# Grove_-_Barometer_Sensor_BME280_v1_0.net
KiCad netlist of a schematic drawn in EAGLE
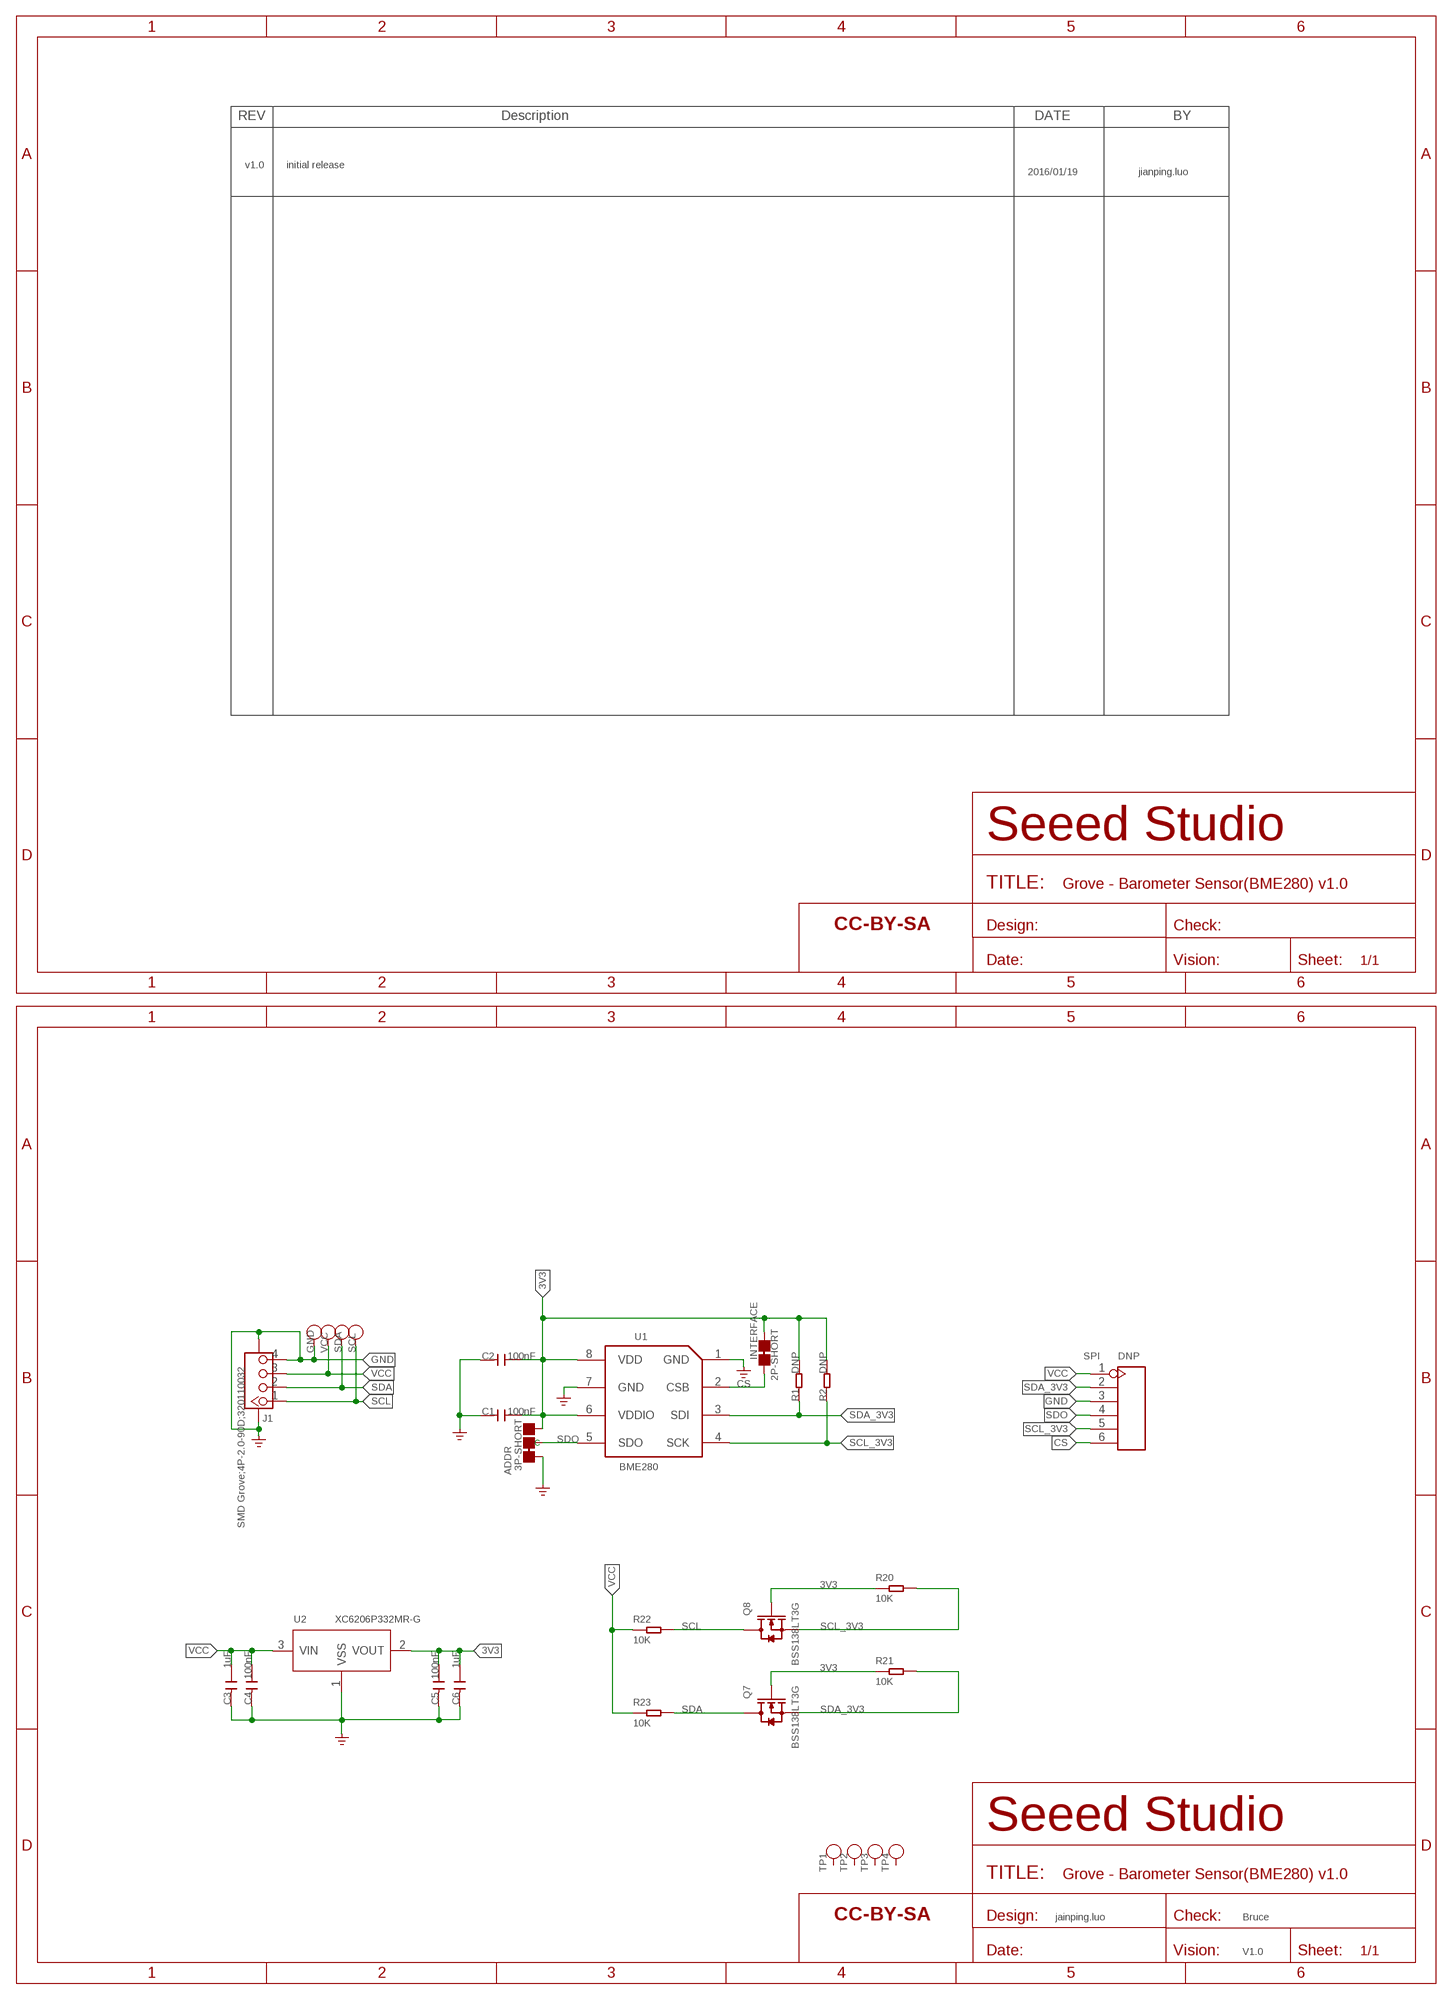
[diagram p0: schematic, sheet 1]

(export (version "E")
  (design (tool "Eeschema 10.0.6"))
  (components
    (comp (ref "ADDR")
      (value "3P-SHORT")
      (footprint "eagle-import:3P-SMD-SHORT")
      (libsource (lib "eagle-import") (part "JUMPER-3P-SHORT"))
    )
    (comp (ref "C1")
      (value "100nF")
      (footprint "eagle-import:C0603")
      (libsource (lib "eagle-import") (part "CAP-0603"))
    )
    (comp (ref "C2")
      (value "100nF")
      (footprint "eagle-import:C0603")
      (libsource (lib "eagle-import") (part "CAP-0603"))
    )
    (comp (ref "C3")
      (value "1uF")
      (footprint "eagle-import:C0603")
      (libsource (lib "eagle-import") (part "CAP-0603"))
    )
    (comp (ref "C4")
      (value "100nF")
      (footprint "eagle-import:C0603")
      (libsource (lib "eagle-import") (part "CAP-0603"))
    )
    (comp (ref "C5")
      (value "100nF")
      (footprint "eagle-import:C0603")
      (libsource (lib "eagle-import") (part "CAP-0603"))
    )
    (comp (ref "C6")
      (value "1uF")
      (footprint "eagle-import:C0603")
      (libsource (lib "eagle-import") (part "CAP-0603"))
    )
    (comp (ref "FR1")
      (value "SEEEDSTUDIO-OPEN-SCH-FRAME")
      (footprint "eagle-import:SEEEDSTUDIO-PCB-FRAME")
      (libsource (lib "eagle-import") (part "SEEEDSTUDIO-OPEN-SCH-FRAME"))
    )
    (comp (ref "FR2")
      (value "SEEEDSTUDIO-OPEN-SCH-FRAME")
      (footprint "eagle-import:SEEEDSTUDIO-PCB-FRAME")
      (libsource (lib "eagle-import") (part "SEEEDSTUDIO-OPEN-SCH-FRAME"))
    )
    (comp (ref "GND")
      (value "TEST-POINT'4545'")
      (footprint "eagle-import:TP-D45MIL")
      (fields (field (name "PARTNO") "DNP"))
      (libsource (lib "eagle-import") (part "TEST-POINT'4545'"))
    )
    (comp (ref "INTERFACE")
      (value "2P-SHORT")
      (footprint "eagle-import:2P-SMD-SHORT")
      (libsource (lib "eagle-import") (part "JUMPER-2P-SHORT"))
    )
    (comp (ref "J1")
      (value "SMD Grove;4P-2.0-90D;320110032")
      (footprint "eagle-import:HW4-SMD-2.0-90D")
      (libsource (lib "eagle-import") (part "GROVE-CONNECTOR-SMD'90D'"))
    )
    (comp (ref "Q7")
      (value "BSS138LT3G")
      (footprint "eagle-import:SOT-23")
      (libsource (lib "eagle-import") (part "MOSFET-N'SOT23'"))
    )
    (comp (ref "Q8")
      (value "BSS138LT3G")
      (footprint "eagle-import:SOT-23")
      (libsource (lib "eagle-import") (part "MOSFET-N'SOT23'"))
    )
    (comp (ref "R1")
      (value "DNP")
      (footprint "eagle-import:R0603")
      (libsource (lib "eagle-import") (part "RES-0603"))
    )
    (comp (ref "R2")
      (value "DNP")
      (footprint "eagle-import:R0603")
      (libsource (lib "eagle-import") (part "RES-0603"))
    )
    (comp (ref "R20")
      (value "10K")
      (footprint "eagle-import:R0603")
      (libsource (lib "eagle-import") (part "RES-0603"))
    )
    (comp (ref "R21")
      (value "10K")
      (footprint "eagle-import:R0603")
      (libsource (lib "eagle-import") (part "RES-0603"))
    )
    (comp (ref "R22")
      (value "10K")
      (footprint "eagle-import:R0603")
      (libsource (lib "eagle-import") (part "RES-0603"))
    )
    (comp (ref "R23")
      (value "10K")
      (footprint "eagle-import:R0603")
      (libsource (lib "eagle-import") (part "RES-0603"))
    )
    (comp (ref "SCL")
      (value "TEST-POINT'4545'")
      (footprint "eagle-import:TP-D45MIL")
      (fields (field (name "PARTNO") "DNP"))
      (libsource (lib "eagle-import") (part "TEST-POINT'4545'"))
    )
    (comp (ref "SDA")
      (value "TEST-POINT'4545'")
      (footprint "eagle-import:TP-D45MIL")
      (fields (field (name "PARTNO") "DNP"))
      (libsource (lib "eagle-import") (part "TEST-POINT'4545'"))
    )
    (comp (ref "SPI")
      (value "DNP")
      (footprint "eagle-import:H6-2.54-C65D35MIL")
      (libsource (lib "eagle-import") (part "HEADER-6P-65/35MIL"))
    )
    (comp (ref "TP1")
      (value "TEST-POINT'4545'")
      (footprint "eagle-import:TP-D45MIL")
      (fields (field (name "PARTNO") "DNP"))
      (libsource (lib "eagle-import") (part "TEST-POINT'4545'"))
    )
    (comp (ref "TP2")
      (value "TEST-POINT'4545'")
      (footprint "eagle-import:TP-D45MIL")
      (fields (field (name "PARTNO") "DNP"))
      (libsource (lib "eagle-import") (part "TEST-POINT'4545'"))
    )
    (comp (ref "TP3")
      (value "TEST-POINT'4545'")
      (footprint "eagle-import:TP-D45MIL")
      (fields (field (name "PARTNO") "DNP"))
      (libsource (lib "eagle-import") (part "TEST-POINT'4545'"))
    )
    (comp (ref "TP4")
      (value "TEST-POINT'4545'")
      (footprint "eagle-import:TP-D45MIL")
      (fields (field (name "PARTNO") "DNP"))
      (libsource (lib "eagle-import") (part "TEST-POINT'4545'"))
    )
    (comp (ref "U1")
      (value "BME280")
      (footprint "eagle-import:LGA8-0.65-2.5X2.5X0.95MM")
      (fields (field (name "MPN") "BST-BME280"))
      (libsource (lib "eagle-import") (part "SENSOR-BME280"))
    )
    (comp (ref "U2")
      (value "XC6206P332MR-G")
      (footprint "eagle-import:SOT-23")
      (libsource (lib "eagle-import") (part "PMIC-XC6206PMR"))
    )
    (comp (ref "VCC")
      (value "TEST-POINT'4545'")
      (footprint "eagle-import:TP-D45MIL")
      (fields (field (name "PARTNO") "DNP"))
      (libsource (lib "eagle-import") (part "TEST-POINT'4545'"))
    )
  )
  (nets
    (net (code "1") (name "3V3") (class "Default")
      (node (ref "ADDR") (pin "00") (pinfunction "R_00") (pintype "bidirectional"))
      (node (ref "C1") (pin "1") (pinfunction "1_1") (pintype "passive"))
      (node (ref "C2") (pin "1") (pinfunction "1_1") (pintype "passive"))
      (node (ref "C5") (pin "1") (pinfunction "1_1") (pintype "passive"))
      (node (ref "C6") (pin "1") (pinfunction "1_1") (pintype "passive"))
      (node (ref "INTERFACE") (pin "2") (pinfunction "2_2") (pintype "bidirectional"))
      (node (ref "Q7") (pin "1") (pinfunction "G_1") (pintype "passive"))
      (node (ref "Q8") (pin "1") (pinfunction "G_1") (pintype "passive"))
      (node (ref "R1") (pin "2") (pinfunction "2_2") (pintype "passive"))
      (node (ref "R2") (pin "2") (pinfunction "2_2") (pintype "passive"))
      (node (ref "R20") (pin "1") (pinfunction "1_1") (pintype "passive"))
      (node (ref "R21") (pin "1") (pinfunction "1_1") (pintype "passive"))
      (node (ref "U1") (pin "6") (pinfunction "VDDIO_6") (pintype "power_in"))
      (node (ref "U1") (pin "8") (pinfunction "VDD_8") (pintype "power_in"))
      (node (ref "U2") (pin "2") (pinfunction "VOUT_2") (pintype "bidirectional"))
    )
    (net (code "2") (name "CS") (class "Default")
      (node (ref "INTERFACE") (pin "1") (pinfunction "1_1") (pintype "bidirectional"))
      (node (ref "SPI") (pin "6") (pinfunction "6_6") (pintype "bidirectional"))
      (node (ref "U1") (pin "2") (pinfunction "CSB_2") (pintype "bidirectional"))
    )
    (net (code "3") (name "GND") (class "Default")
      (node (ref "ADDR") (pin "11") (pinfunction "L_11") (pintype "bidirectional"))
      (node (ref "C1") (pin "2") (pinfunction "2_2") (pintype "passive"))
      (node (ref "C2") (pin "2") (pinfunction "2_2") (pintype "passive"))
      (node (ref "C3") (pin "2") (pinfunction "2_2") (pintype "passive"))
      (node (ref "C4") (pin "2") (pinfunction "2_2") (pintype "passive"))
      (node (ref "C5") (pin "2") (pinfunction "2_2") (pintype "passive"))
      (node (ref "C6") (pin "2") (pinfunction "2_2") (pintype "passive"))
      (node (ref "GND") (pin "T") (pinfunction "T_T") (pintype "bidirectional"))
      (node (ref "J1") (pin "4") (pinfunction "4_4") (pintype "bidirectional"))
      (node (ref "J1") (pin "SS1") (pinfunction "SS1_SS1") (pintype "bidirectional"))
      (node (ref "J1") (pin "SS2") (pinfunction "SS2_SS2") (pintype "bidirectional"))
      (node (ref "SPI") (pin "3") (pinfunction "3_3") (pintype "bidirectional"))
      (node (ref "U1") (pin "1") (pinfunction "GND_1") (pintype "power_in"))
      (node (ref "U1") (pin "7") (pinfunction "GND_7") (pintype "power_in"))
      (node (ref "U2") (pin "1") (pinfunction "VSS_1") (pintype "bidirectional"))
    )
    (net (code "4") (name "SCL") (class "Default")
      (node (ref "J1") (pin "1") (pinfunction "1_1") (pintype "bidirectional"))
      (node (ref "Q8") (pin "3") (pinfunction "D_3") (pintype "passive"))
      (node (ref "R22") (pin "2") (pinfunction "2_2") (pintype "passive"))
      (node (ref "SCL") (pin "T") (pinfunction "T_T") (pintype "bidirectional"))
    )
    (net (code "5") (name "SCL_3V3") (class "Default")
      (node (ref "Q8") (pin "2") (pinfunction "S_2") (pintype "passive"))
      (node (ref "R2") (pin "1") (pinfunction "1_1") (pintype "passive"))
      (node (ref "R20") (pin "2") (pinfunction "2_2") (pintype "passive"))
      (node (ref "SPI") (pin "5") (pinfunction "5_5") (pintype "bidirectional"))
      (node (ref "U1") (pin "4") (pinfunction "SCK_4") (pintype "bidirectional"))
    )
    (net (code "6") (name "SDA") (class "Default")
      (node (ref "J1") (pin "2") (pinfunction "2_2") (pintype "bidirectional"))
      (node (ref "Q7") (pin "3") (pinfunction "D_3") (pintype "passive"))
      (node (ref "R23") (pin "2") (pinfunction "2_2") (pintype "passive"))
      (node (ref "SDA") (pin "T") (pinfunction "T_T") (pintype "bidirectional"))
    )
    (net (code "7") (name "SDA_3V3") (class "Default")
      (node (ref "Q7") (pin "2") (pinfunction "S_2") (pintype "passive"))
      (node (ref "R1") (pin "1") (pinfunction "1_1") (pintype "passive"))
      (node (ref "R21") (pin "2") (pinfunction "2_2") (pintype "passive"))
      (node (ref "SPI") (pin "2") (pinfunction "2_2") (pintype "bidirectional"))
      (node (ref "U1") (pin "3") (pinfunction "SDI_3") (pintype "bidirectional"))
    )
    (net (code "8") (name "SDO") (class "Default")
      (node (ref "ADDR") (pin "MM") (pinfunction "C_MM") (pintype "bidirectional"))
      (node (ref "SPI") (pin "4") (pinfunction "4_4") (pintype "bidirectional"))
      (node (ref "U1") (pin "5") (pinfunction "SDO_5") (pintype "bidirectional"))
    )
    (net (code "9") (name "VCC") (class "Default")
      (node (ref "C3") (pin "1") (pinfunction "1_1") (pintype "passive"))
      (node (ref "C4") (pin "1") (pinfunction "1_1") (pintype "passive"))
      (node (ref "J1") (pin "3") (pinfunction "3_3") (pintype "bidirectional"))
      (node (ref "R22") (pin "1") (pinfunction "1_1") (pintype "passive"))
      (node (ref "R23") (pin "1") (pinfunction "1_1") (pintype "passive"))
      (node (ref "SPI") (pin "1") (pinfunction "1_1") (pintype "bidirectional"))
      (node (ref "U2") (pin "3") (pinfunction "VIN_3") (pintype "bidirectional"))
      (node (ref "VCC") (pin "T") (pinfunction "T_T") (pintype "bidirectional"))
    )
    (net (code "10") (name "unconnected-(TP1-PadT)") (class "Default")
      (node (ref "TP1") (pin "T") (pinfunction "T_T") (pintype "bidirectional"))
    )
    (net (code "11") (name "unconnected-(TP2-PadT)") (class "Default")
      (node (ref "TP2") (pin "T") (pinfunction "T_T") (pintype "bidirectional"))
    )
    (net (code "12") (name "unconnected-(TP3-PadT)") (class "Default")
      (node (ref "TP3") (pin "T") (pinfunction "T_T") (pintype "bidirectional"))
    )
    (net (code "13") (name "unconnected-(TP4-PadT)") (class "Default")
      (node (ref "TP4") (pin "T") (pinfunction "T_T") (pintype "bidirectional"))
    )
  )
)
